# MainSheet.net
KiCad netlist of a schematic drawn in Altium Designer
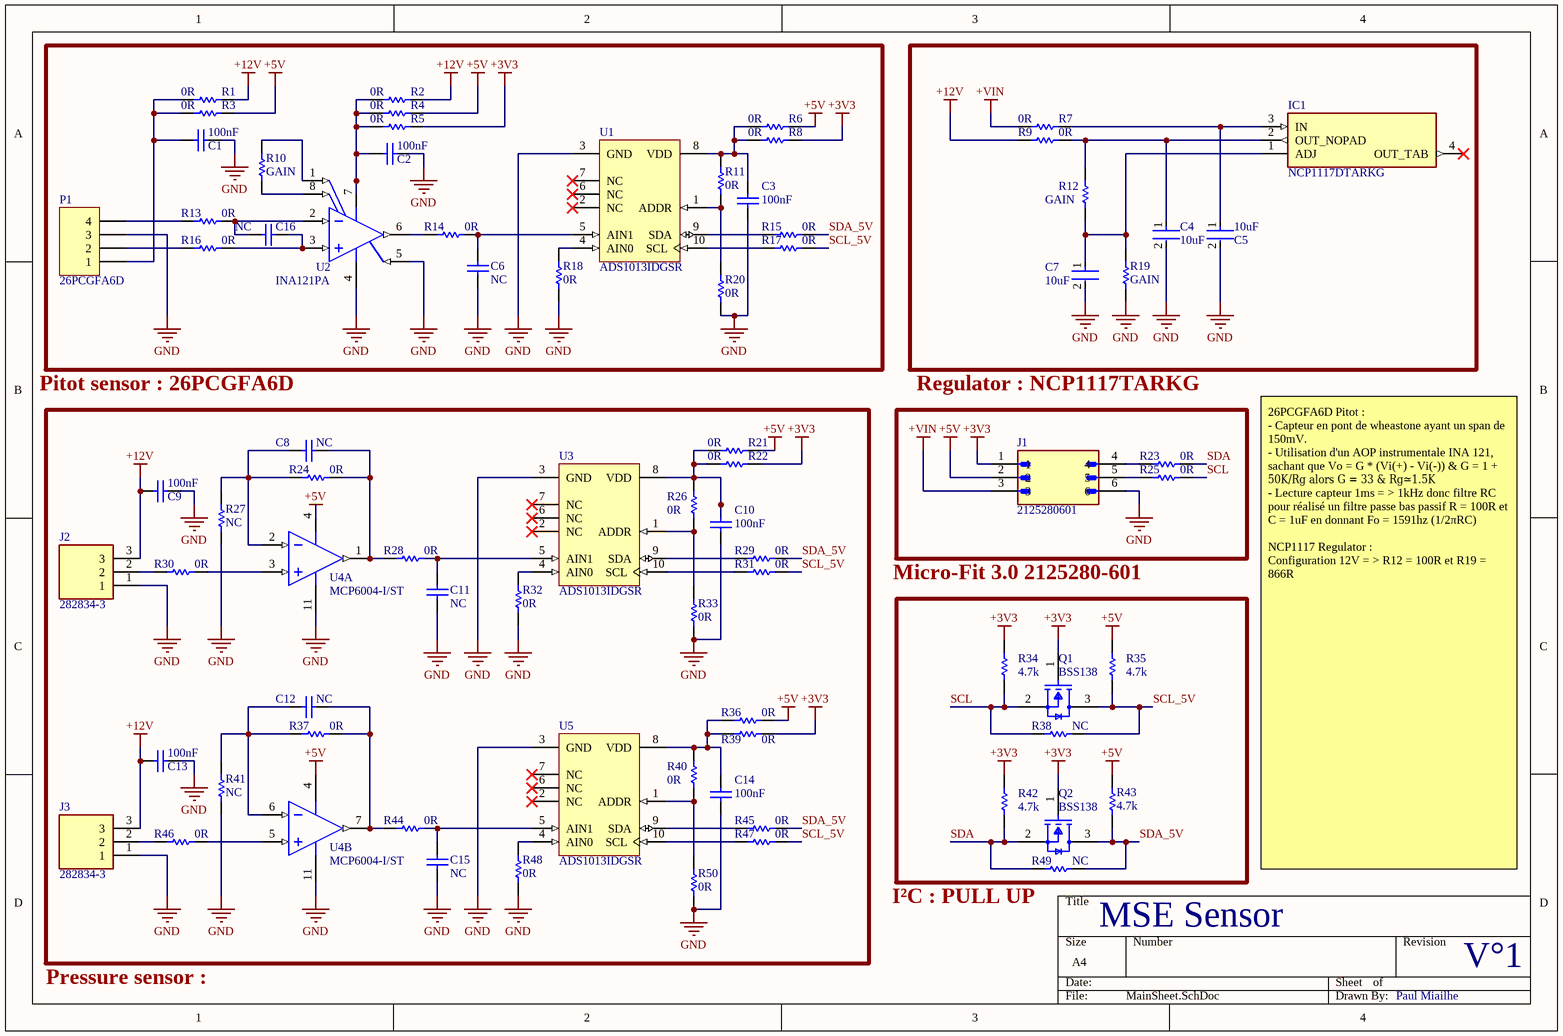
[diagram p0: MainSheet.SchDoc]

(export (version "E")
  (design (tool "Eeschema 10.0.6"))
  (components
    (comp (ref "C1")
      (value "GRM21BR71H104KA01L")
      (footprint "CAPC2013X135X45ML10T25")
      (description "Chip Capacitor, 0.1 uF, +/- 10%, 50 V, -55 to 125 degC, 0805 (2012 Metric), RoHS, Tape and Reel")
      (fields
        (field (name "VOLTAGE") "50V")
        (field (name "CAPACITANCE") "100nF")
        (field (name "TOLERANCE") "10%")
      )
      (libsource (lib "Altium Content Vault") (part "CAP-NP-2"))
    )
    (comp (ref "C2")
      (value "GRM21BR71H104KA01L")
      (footprint "CAPC2013X135X45ML10T25")
      (description "Chip Capacitor, 0.1 uF, +/- 10%, 50 V, -55 to 125 degC, 0805 (2012 Metric), RoHS, Tape and Reel")
      (fields
        (field (name "VOLTAGE") "50V")
        (field (name "CAPACITANCE") "100nF")
        (field (name "TOLERANCE") "10%")
      )
      (libsource (lib "Altium Content Vault") (part "CAP-NP-2"))
    )
    (comp (ref "C3")
      (value "GRM21BR71H104KA01L")
      (footprint "CAPC2013X135X45ML10T25")
      (description "Chip Capacitor, 0.1 uF, +/- 10%, 50 V, -55 to 125 degC, 0805 (2012 Metric), RoHS, Tape and Reel")
      (fields
        (field (name "VOLTAGE") "50V")
        (field (name "CAPACITANCE") "100nF")
        (field (name "TOLERANCE") "10%")
      )
      (libsource (lib "Altium Content Vault") (part "CAP-NP-2"))
    )
    (comp (ref "C4")
      (value "GRM21BR61E106KA73L")
      (footprint "FP-GRM21B-0_15-IPC_C")
      (description "Chip Multilayer Ceramic Capacitors for General Purpose, 0805, 10uF, X5R, 15%, 10%, 25V")
      (fields
        (field (name "VOLTAGE") "25V")
        (field (name "CAPACITANCE") "10uF")
        (field (name "TOLERANCE") "10%")
      )
      (libsource (lib "Altium Content Vault") (part "b4654b650e69147ec39a6b967a45e02"))
    )
    (comp (ref "C5")
      (value "GRM21BR61E106KA73L")
      (footprint "FP-GRM21B-0_15-IPC_C")
      (description "Chip Multilayer Ceramic Capacitors for General Purpose, 0805, 10uF, X5R, 15%, 10%, 25V")
      (fields
        (field (name "VOLTAGE") "25V")
        (field (name "CAPACITANCE") "10uF")
        (field (name "TOLERANCE") "10%")
      )
      (libsource (lib "Altium Content Vault") (part "b4654b650e69147ec39a6b967a45e02"))
    )
    (comp (ref "C6")
      (value "GRM21BR71H104KA01L")
      (footprint "CAPC2013X135X45ML10T25")
      (description "Chip Capacitor, 0.1 uF, +/- 10%, 50 V, -55 to 125 degC, 0805 (2012 Metric), RoHS, Tape and Reel")
      (fields
        (field (name "VOLTAGE") "50V")
        (field (name "CAPACITANCE") "NC")
        (field (name "TOLERANCE") "10%")
      )
      (libsource (lib "Altium Content Vault") (part "CAP-NP-2"))
    )
    (comp (ref "C7")
      (value "GRM21BR61E106KA73L")
      (footprint "FP-GRM21B-0_15-IPC_C")
      (description "Chip Multilayer Ceramic Capacitors for General Purpose, 0805, 10uF, X5R, 15%, 10%, 25V")
      (fields
        (field (name "VOLTAGE") "25V")
        (field (name "CAPACITANCE") "10uF")
        (field (name "TOLERANCE") "10%")
      )
      (libsource (lib "Altium Content Vault") (part "b4654b650e69147ec39a6b967a45e02"))
    )
    (comp (ref "C8")
      (value "GRM21BR71H104KA01L")
      (footprint "CAPC2013X135X45ML10T25")
      (description "Chip Capacitor, 0.1 uF, +/- 10%, 50 V, -55 to 125 degC, 0805 (2012 Metric), RoHS, Tape and Reel")
      (fields
        (field (name "VOLTAGE") "50V")
        (field (name "CAPACITANCE") "NC")
        (field (name "TOLERANCE") "10%")
      )
      (libsource (lib "Altium Content Vault") (part "CAP-NP-2"))
    )
    (comp (ref "C9")
      (value "GRM21BR71H104KA01L")
      (footprint "CAPC2013X135X45ML10T25")
      (description "Chip Capacitor, 0.1 uF, +/- 10%, 50 V, -55 to 125 degC, 0805 (2012 Metric), RoHS, Tape and Reel")
      (fields
        (field (name "VOLTAGE") "50V")
        (field (name "CAPACITANCE") "100nF")
        (field (name "TOLERANCE") "10%")
      )
      (libsource (lib "Altium Content Vault") (part "CAP-NP-2"))
    )
    (comp (ref "C10")
      (value "GRM21BR71H104KA01L")
      (footprint "CAPC2013X135X45ML10T25")
      (description "Chip Capacitor, 0.1 uF, +/- 10%, 50 V, -55 to 125 degC, 0805 (2012 Metric), RoHS, Tape and Reel")
      (fields
        (field (name "VOLTAGE") "50V")
        (field (name "CAPACITANCE") "100nF")
        (field (name "TOLERANCE") "10%")
      )
      (libsource (lib "Altium Content Vault") (part "CAP-NP-2"))
    )
    (comp (ref "C11")
      (value "GRM21BR71H104KA01L")
      (footprint "CAPC2013X135X45ML10T25")
      (description "Chip Capacitor, 0.1 uF, +/- 10%, 50 V, -55 to 125 degC, 0805 (2012 Metric), RoHS, Tape and Reel")
      (fields
        (field (name "VOLTAGE") "50V")
        (field (name "CAPACITANCE") "NC")
        (field (name "TOLERANCE") "10%")
      )
      (libsource (lib "Altium Content Vault") (part "CAP-NP-2"))
    )
    (comp (ref "C12")
      (value "GRM21BR71H104KA01L")
      (footprint "CAPC2013X135X45ML10T25")
      (description "Chip Capacitor, 0.1 uF, +/- 10%, 50 V, -55 to 125 degC, 0805 (2012 Metric), RoHS, Tape and Reel")
      (fields
        (field (name "VOLTAGE") "50V")
        (field (name "CAPACITANCE") "NC")
        (field (name "TOLERANCE") "10%")
      )
      (libsource (lib "Altium Content Vault") (part "CAP-NP-2"))
    )
    (comp (ref "C13")
      (value "GRM21BR71H104KA01L")
      (footprint "CAPC2013X135X45ML10T25")
      (description "Chip Capacitor, 0.1 uF, +/- 10%, 50 V, -55 to 125 degC, 0805 (2012 Metric), RoHS, Tape and Reel")
      (fields
        (field (name "VOLTAGE") "50V")
        (field (name "CAPACITANCE") "100nF")
        (field (name "TOLERANCE") "10%")
      )
      (libsource (lib "Altium Content Vault") (part "CAP-NP-2"))
    )
    (comp (ref "C14")
      (value "GRM21BR71H104KA01L")
      (footprint "CAPC2013X135X45ML10T25")
      (description "Chip Capacitor, 0.1 uF, +/- 10%, 50 V, -55 to 125 degC, 0805 (2012 Metric), RoHS, Tape and Reel")
      (fields
        (field (name "VOLTAGE") "50V")
        (field (name "CAPACITANCE") "100nF")
        (field (name "TOLERANCE") "10%")
      )
      (libsource (lib "Altium Content Vault") (part "CAP-NP-2"))
    )
    (comp (ref "C15")
      (value "GRM21BR71H104KA01L")
      (footprint "CAPC2013X135X45ML10T25")
      (description "Chip Capacitor, 0.1 uF, +/- 10%, 50 V, -55 to 125 degC, 0805 (2012 Metric), RoHS, Tape and Reel")
      (fields
        (field (name "VOLTAGE") "50V")
        (field (name "CAPACITANCE") "NC")
        (field (name "TOLERANCE") "10%")
      )
      (libsource (lib "Altium Content Vault") (part "CAP-NP-2"))
    )
    (comp (ref "C16")
      (value "GRM21BR71H104KA01L")
      (footprint "CAPC2013X135X45ML10T25")
      (description "Chip Capacitor, 0.1 uF, +/- 10%, 50 V, -55 to 125 degC, 0805 (2012 Metric), RoHS, Tape and Reel")
      (fields
        (field (name "VOLTAGE") "50V")
        (field (name "CAPACITANCE") "NC")
        (field (name "TOLERANCE") "10%")
      )
      (libsource (lib "Altium Content Vault") (part "CAP-NP-2"))
    )
    (comp (ref "IC1")
      (value "NCP1117DTARKG")
      (footprint "SamacSys:TO229P990X238-4N")
      (description "Integrated Circuit")
      (fields (field (name "MOUSER PART NUMBER") "863-NCP1117DTARKG"))
      (libsource (lib "*") (part "NCP1117DTARKG"))
    )
    (comp (ref "J1")
      (value "2125280601")
      (footprint "MOLEX_2125280601")
      (description "Connector Header Through Hole, Right Angle 6 position 0.118 (3.00mm)")
      (fields (field (name "MF") "Molex"))
      (libsource (lib "Saint-Étienne School of Mines- Mines Space") (part "2125280601"))
    )
    (comp (ref "J2")
      (value "282834-3")
      (footprint "SamacSys:2828343")
      (description "Connector")
      (fields (field (name "MOUSER PART NUMBER") "571-2828343"))
      (libsource (lib "*") (part "282834-3"))
    )
    (comp (ref "J3")
      (value "282834-3")
      (footprint "SamacSys:2828343")
      (description "Connector")
      (fields (field (name "MOUSER PART NUMBER") "571-2828343"))
      (libsource (lib "*") (part "282834-3"))
    )
    (comp (ref "P1")
      (value "26PCGFA6D")
      (footprint "HDR1X4")
      (description "Header, 4-Pin")
      (fields (field (name "PUBLISHER") "Altium Limited"))
      (libsource (lib "Miscellaneous Connectors") (part "Header 4"))
    )
    (comp (ref "Q1")
      (value "BSS138")
      (footprint "FP-318-08-IPC_B")
      (description "MOSFET N-CH 50V 220MA SOT-23")
      (libsource (lib "Altium Content Vault") (part "3b9c635fedb024a5347a57b145af9cc"))
    )
    (comp (ref "Q2")
      (value "BSS138")
      (footprint "FP-318-08-IPC_B")
      (description "MOSFET N-CH 50V 220MA SOT-23")
      (libsource (lib "Altium Content Vault") (part "3b9c635fedb024a5347a57b145af9cc"))
    )
    (comp (ref "R1")
      (value "0R")
      (footprint "RESC1608X55X25ML10T15")
      (description "Chip Resistor, 0 Ohm, +/- 5%, 0.1 W, -55 to 155 degC, 0603 (1608 Metric), RoHS, Tape and Reel")
      (fields (field (name "TOLERANCE") "5%") (field (name "MANUFACTURER") "Yageo"))
      (libsource (lib "Altium Content Vault") (part "RES-2"))
    )
    (comp (ref "R2")
      (value "0R")
      (footprint "RESC1608X55X25ML10T15")
      (description "Chip Resistor, 0 Ohm, +/- 5%, 0.1 W, -55 to 155 degC, 0603 (1608 Metric), RoHS, Tape and Reel")
      (fields (field (name "TOLERANCE") "5%") (field (name "MANUFACTURER") "Yageo"))
      (libsource (lib "Altium Content Vault") (part "RES-2"))
    )
    (comp (ref "R3")
      (value "0R")
      (footprint "RESC1608X55X25ML10T15")
      (description "Chip Resistor, 0 Ohm, +/- 5%, 0.1 W, -55 to 155 degC, 0603 (1608 Metric), RoHS, Tape and Reel")
      (fields (field (name "TOLERANCE") "5%") (field (name "MANUFACTURER") "Yageo"))
      (libsource (lib "Altium Content Vault") (part "RES-2"))
    )
    (comp (ref "R4")
      (value "0R")
      (footprint "RESC1608X55X25ML10T15")
      (description "Chip Resistor, 0 Ohm, +/- 5%, 0.1 W, -55 to 155 degC, 0603 (1608 Metric), RoHS, Tape and Reel")
      (fields (field (name "TOLERANCE") "5%") (field (name "MANUFACTURER") "Yageo"))
      (libsource (lib "Altium Content Vault") (part "RES-2"))
    )
    (comp (ref "R5")
      (value "0R")
      (footprint "RESC1608X55X25ML10T15")
      (description "Chip Resistor, 0 Ohm, +/- 5%, 0.1 W, -55 to 155 degC, 0603 (1608 Metric), RoHS, Tape and Reel")
      (fields (field (name "TOLERANCE") "5%") (field (name "MANUFACTURER") "Yageo"))
      (libsource (lib "Altium Content Vault") (part "RES-2"))
    )
    (comp (ref "R6")
      (value "0R")
      (footprint "RESC1608X55X25ML10T15")
      (description "Chip Resistor, 0 Ohm, +/- 5%, 0.1 W, -55 to 155 degC, 0603 (1608 Metric), RoHS, Tape and Reel")
      (fields (field (name "TOLERANCE") "5%") (field (name "MANUFACTURER") "Yageo"))
      (libsource (lib "Altium Content Vault") (part "RES-2"))
    )
    (comp (ref "R7")
      (value "0R")
      (footprint "RESC1608X55X25ML10T15")
      (description "Chip Resistor, 0 Ohm, +/- 5%, 0.1 W, -55 to 155 degC, 0603 (1608 Metric), RoHS, Tape and Reel")
      (fields (field (name "TOLERANCE") "5%") (field (name "MANUFACTURER") "Yageo"))
      (libsource (lib "Altium Content Vault") (part "RES-2"))
    )
    (comp (ref "R8")
      (value "0R")
      (footprint "RESC1608X55X25ML10T15")
      (description "Chip Resistor, 0 Ohm, +/- 5%, 0.1 W, -55 to 155 degC, 0603 (1608 Metric), RoHS, Tape and Reel")
      (fields (field (name "TOLERANCE") "5%") (field (name "MANUFACTURER") "Yageo"))
      (libsource (lib "Altium Content Vault") (part "RES-2"))
    )
    (comp (ref "R9")
      (value "0R")
      (footprint "RESC1608X55X25ML10T15")
      (description "Chip Resistor, 0 Ohm, +/- 5%, 0.1 W, -55 to 155 degC, 0603 (1608 Metric), RoHS, Tape and Reel")
      (fields (field (name "TOLERANCE") "5%") (field (name "MANUFACTURER") "Yageo"))
      (libsource (lib "Altium Content Vault") (part "RES-2"))
    )
    (comp (ref "R10")
      (value "GAIN")
      (footprint "RESC1608X55X25ML10T15")
      (description "Chip Resistor, 0 Ohm, +/- 5%, 0.1 W, -55 to 155 degC, 0603 (1608 Metric), RoHS, Tape and Reel")
      (fields (field (name "TOLERANCE") "5%") (field (name "MANUFACTURER") "Yageo"))
      (libsource (lib "Altium Content Vault") (part "RES-2"))
    )
    (comp (ref "R11")
      (value "0R")
      (footprint "RESC1608X55X25ML10T15")
      (description "Chip Resistor, 0 Ohm, +/- 5%, 0.1 W, -55 to 155 degC, 0603 (1608 Metric), RoHS, Tape and Reel")
      (fields (field (name "TOLERANCE") "5%") (field (name "MANUFACTURER") "Yageo"))
      (libsource (lib "Altium Content Vault") (part "RES-2"))
    )
    (comp (ref "R12")
      (value "GAIN")
      (footprint "RESC1608X55X25ML10T15")
      (description "Chip Resistor, 0 Ohm, +/- 5%, 0.1 W, -55 to 155 degC, 0603 (1608 Metric), RoHS, Tape and Reel")
      (fields (field (name "TOLERANCE") "5%") (field (name "MANUFACTURER") "Yageo"))
      (libsource (lib "Altium Content Vault") (part "RES-2"))
    )
    (comp (ref "R13")
      (value "0R")
      (footprint "RESC1608X55X25ML10T15")
      (description "Chip Resistor, 0 Ohm, +/- 5%, 0.1 W, -55 to 155 degC, 0603 (1608 Metric), RoHS, Tape and Reel")
      (fields (field (name "TOLERANCE") "5%") (field (name "MANUFACTURER") "Yageo"))
      (libsource (lib "Altium Content Vault") (part "RES-2"))
    )
    (comp (ref "R14")
      (value "0R")
      (footprint "RESC1608X55X25ML10T15")
      (description "Chip Resistor, 0 Ohm, +/- 5%, 0.1 W, -55 to 155 degC, 0603 (1608 Metric), RoHS, Tape and Reel")
      (fields (field (name "TOLERANCE") "5%") (field (name "MANUFACTURER") "Yageo"))
      (libsource (lib "Altium Content Vault") (part "RES-2"))
    )
    (comp (ref "R15")
      (value "0R")
      (footprint "RESC1608X55X25ML10T15")
      (description "Chip Resistor, 0 Ohm, +/- 5%, 0.1 W, -55 to 155 degC, 0603 (1608 Metric), RoHS, Tape and Reel")
      (fields (field (name "TOLERANCE") "5%") (field (name "MANUFACTURER") "Yageo"))
      (libsource (lib "Altium Content Vault") (part "RES-2"))
    )
    (comp (ref "R16")
      (value "0R")
      (footprint "RESC1608X55X25ML10T15")
      (description "Chip Resistor, 0 Ohm, +/- 5%, 0.1 W, -55 to 155 degC, 0603 (1608 Metric), RoHS, Tape and Reel")
      (fields (field (name "TOLERANCE") "5%") (field (name "MANUFACTURER") "Yageo"))
      (libsource (lib "Altium Content Vault") (part "RES-2"))
    )
    (comp (ref "R17")
      (value "0R")
      (footprint "RESC1608X55X25ML10T15")
      (description "Chip Resistor, 0 Ohm, +/- 5%, 0.1 W, -55 to 155 degC, 0603 (1608 Metric), RoHS, Tape and Reel")
      (fields (field (name "TOLERANCE") "5%") (field (name "MANUFACTURER") "Yageo"))
      (libsource (lib "Altium Content Vault") (part "RES-2"))
    )
    (comp (ref "R18")
      (value "0R")
      (footprint "RESC1608X55X25ML10T15")
      (description "Chip Resistor, 0 Ohm, +/- 5%, 0.1 W, -55 to 155 degC, 0603 (1608 Metric), RoHS, Tape and Reel")
      (fields (field (name "TOLERANCE") "5%") (field (name "MANUFACTURER") "Yageo"))
      (libsource (lib "Altium Content Vault") (part "RES-2"))
    )
    (comp (ref "R19")
      (value "GAIN")
      (footprint "RESC1608X55X25ML10T15")
      (description "Chip Resistor, 0 Ohm, +/- 5%, 0.1 W, -55 to 155 degC, 0603 (1608 Metric), RoHS, Tape and Reel")
      (fields (field (name "TOLERANCE") "5%") (field (name "MANUFACTURER") "Yageo"))
      (libsource (lib "Altium Content Vault") (part "RES-2"))
    )
    (comp (ref "R20")
      (value "0R")
      (footprint "RESC1608X55X25ML10T15")
      (description "Chip Resistor, 0 Ohm, +/- 5%, 0.1 W, -55 to 155 degC, 0603 (1608 Metric), RoHS, Tape and Reel")
      (fields (field (name "TOLERANCE") "5%") (field (name "MANUFACTURER") "Yageo"))
      (libsource (lib "Altium Content Vault") (part "RES-2"))
    )
    (comp (ref "R21")
      (value "0R")
      (footprint "RESC1608X55X25ML10T15")
      (description "Chip Resistor, 0 Ohm, +/- 5%, 0.1 W, -55 to 155 degC, 0603 (1608 Metric), RoHS, Tape and Reel")
      (fields (field (name "TOLERANCE") "5%") (field (name "MANUFACTURER") "Yageo"))
      (libsource (lib "Altium Content Vault") (part "RES-2"))
    )
    (comp (ref "R22")
      (value "0R")
      (footprint "RESC1608X55X25ML10T15")
      (description "Chip Resistor, 0 Ohm, +/- 5%, 0.1 W, -55 to 155 degC, 0603 (1608 Metric), RoHS, Tape and Reel")
      (fields (field (name "TOLERANCE") "5%") (field (name "MANUFACTURER") "Yageo"))
      (libsource (lib "Altium Content Vault") (part "RES-2"))
    )
    (comp (ref "R23")
      (value "0R")
      (footprint "RESC1608X55X25ML10T15")
      (description "Chip Resistor, 0 Ohm, +/- 5%, 0.1 W, -55 to 155 degC, 0603 (1608 Metric), RoHS, Tape and Reel")
      (fields (field (name "TOLERANCE") "5%") (field (name "MANUFACTURER") "Yageo"))
      (libsource (lib "Altium Content Vault") (part "RES-2"))
    )
    (comp (ref "R24")
      (value "0R")
      (footprint "RESC1608X55X25ML10T15")
      (description "Chip Resistor, 0 Ohm, +/- 5%, 0.1 W, -55 to 155 degC, 0603 (1608 Metric), RoHS, Tape and Reel")
      (fields (field (name "TOLERANCE") "5%") (field (name "MANUFACTURER") "Yageo"))
      (libsource (lib "Altium Content Vault") (part "RES-2"))
    )
    (comp (ref "R25")
      (value "0R")
      (footprint "RESC1608X55X25ML10T15")
      (description "Chip Resistor, 0 Ohm, +/- 5%, 0.1 W, -55 to 155 degC, 0603 (1608 Metric), RoHS, Tape and Reel")
      (fields (field (name "TOLERANCE") "5%") (field (name "MANUFACTURER") "Yageo"))
      (libsource (lib "Altium Content Vault") (part "RES-2"))
    )
    (comp (ref "R26")
      (value "0R")
      (footprint "RESC1608X55X25ML10T15")
      (description "Chip Resistor, 0 Ohm, +/- 5%, 0.1 W, -55 to 155 degC, 0603 (1608 Metric), RoHS, Tape and Reel")
      (fields (field (name "TOLERANCE") "5%") (field (name "MANUFACTURER") "Yageo"))
      (libsource (lib "Altium Content Vault") (part "RES-2"))
    )
    (comp (ref "R27")
      (value "NC")
      (footprint "RESC1608X55X25ML10T15")
      (description "Chip Resistor, 0 Ohm, +/- 5%, 0.1 W, -55 to 155 degC, 0603 (1608 Metric), RoHS, Tape and Reel")
      (fields (field (name "TOLERANCE") "5%") (field (name "MANUFACTURER") "Yageo"))
      (libsource (lib "Altium Content Vault") (part "RES-2"))
    )
    (comp (ref "R28")
      (value "0R")
      (footprint "RESC1608X55X25ML10T15")
      (description "Chip Resistor, 0 Ohm, +/- 5%, 0.1 W, -55 to 155 degC, 0603 (1608 Metric), RoHS, Tape and Reel")
      (fields (field (name "TOLERANCE") "5%") (field (name "MANUFACTURER") "Yageo"))
      (libsource (lib "Altium Content Vault") (part "RES-2"))
    )
    (comp (ref "R29")
      (value "0R")
      (footprint "RESC1608X55X25ML10T15")
      (description "Chip Resistor, 0 Ohm, +/- 5%, 0.1 W, -55 to 155 degC, 0603 (1608 Metric), RoHS, Tape and Reel")
      (fields (field (name "TOLERANCE") "5%") (field (name "MANUFACTURER") "Yageo"))
      (libsource (lib "Altium Content Vault") (part "RES-2"))
    )
    (comp (ref "R30")
      (value "0R")
      (footprint "RESC1608X55X25ML10T15")
      (description "Chip Resistor, 0 Ohm, +/- 5%, 0.1 W, -55 to 155 degC, 0603 (1608 Metric), RoHS, Tape and Reel")
      (fields (field (name "TOLERANCE") "5%") (field (name "MANUFACTURER") "Yageo"))
      (libsource (lib "Altium Content Vault") (part "RES-2"))
    )
    (comp (ref "R31")
      (value "0R")
      (footprint "RESC1608X55X25ML10T15")
      (description "Chip Resistor, 0 Ohm, +/- 5%, 0.1 W, -55 to 155 degC, 0603 (1608 Metric), RoHS, Tape and Reel")
      (fields (field (name "TOLERANCE") "5%") (field (name "MANUFACTURER") "Yageo"))
      (libsource (lib "Altium Content Vault") (part "RES-2"))
    )
    (comp (ref "R32")
      (value "0R")
      (footprint "RESC1608X55X25ML10T15")
      (description "Chip Resistor, 0 Ohm, +/- 5%, 0.1 W, -55 to 155 degC, 0603 (1608 Metric), RoHS, Tape and Reel")
      (fields (field (name "TOLERANCE") "5%") (field (name "MANUFACTURER") "Yageo"))
      (libsource (lib "Altium Content Vault") (part "RES-2"))
    )
    (comp (ref "R33")
      (value "0R")
      (footprint "RESC1608X55X25ML10T15")
      (description "Chip Resistor, 0 Ohm, +/- 5%, 0.1 W, -55 to 155 degC, 0603 (1608 Metric), RoHS, Tape and Reel")
      (fields (field (name "TOLERANCE") "5%") (field (name "MANUFACTURER") "Yageo"))
      (libsource (lib "Altium Content Vault") (part "RES-2"))
    )
    (comp (ref "R34")
      (value "RC0603FR-074K7L")
      (footprint "RESC1608X55X25LL10T15")
      (description "Chip Resistor, 4.7 KOhm, +/- 1%, 0.1 W, -55 to 155 degC, 0603 (1608 Metric), RoHS, Tape and Reel")
      (fields
        (field (name "MANUFACTURER") "Yageo")
        (field (name "RESISTANCE") "4.7k")
        (field (name "TOLERANCE") "1%")
      )
      (libsource (lib "Altium Content Vault") (part "RES-2"))
    )
    (comp (ref "R35")
      (value "RC0603FR-074K7L")
      (footprint "RESC1608X55X25LL10T15")
      (description "Chip Resistor, 4.7 KOhm, +/- 1%, 0.1 W, -55 to 155 degC, 0603 (1608 Metric), RoHS, Tape and Reel")
      (fields
        (field (name "MANUFACTURER") "Yageo")
        (field (name "RESISTANCE") "4.7k")
        (field (name "TOLERANCE") "1%")
      )
      (libsource (lib "Altium Content Vault") (part "RES-2"))
    )
    (comp (ref "R36")
      (value "0R")
      (footprint "RESC1608X55X25ML10T15")
      (description "Chip Resistor, 0 Ohm, +/- 5%, 0.1 W, -55 to 155 degC, 0603 (1608 Metric), RoHS, Tape and Reel")
      (fields (field (name "TOLERANCE") "5%") (field (name "MANUFACTURER") "Yageo"))
      (libsource (lib "Altium Content Vault") (part "RES-2"))
    )
    (comp (ref "R37")
      (value "0R")
      (footprint "RESC1608X55X25ML10T15")
      (description "Chip Resistor, 0 Ohm, +/- 5%, 0.1 W, -55 to 155 degC, 0603 (1608 Metric), RoHS, Tape and Reel")
      (fields (field (name "TOLERANCE") "5%") (field (name "MANUFACTURER") "Yageo"))
      (libsource (lib "Altium Content Vault") (part "RES-2"))
    )
    (comp (ref "R38")
      (value "NC")
      (footprint "RESC1608X55X25ML10T15")
      (description "Chip Resistor, 0 Ohm, +/- 5%, 0.1 W, -55 to 155 degC, 0603 (1608 Metric), RoHS, Tape and Reel")
      (fields (field (name "TOLERANCE") "5%") (field (name "MANUFACTURER") "Yageo"))
      (libsource (lib "Altium Content Vault") (part "RES-2"))
    )
    (comp (ref "R39")
      (value "0R")
      (footprint "RESC1608X55X25ML10T15")
      (description "Chip Resistor, 0 Ohm, +/- 5%, 0.1 W, -55 to 155 degC, 0603 (1608 Metric), RoHS, Tape and Reel")
      (fields (field (name "TOLERANCE") "5%") (field (name "MANUFACTURER") "Yageo"))
      (libsource (lib "Altium Content Vault") (part "RES-2"))
    )
    (comp (ref "R40")
      (value "0R")
      (footprint "RESC1608X55X25ML10T15")
      (description "Chip Resistor, 0 Ohm, +/- 5%, 0.1 W, -55 to 155 degC, 0603 (1608 Metric), RoHS, Tape and Reel")
      (fields (field (name "TOLERANCE") "5%") (field (name "MANUFACTURER") "Yageo"))
      (libsource (lib "Altium Content Vault") (part "RES-2"))
    )
    (comp (ref "R41")
      (value "NC")
      (footprint "RESC1608X55X25ML10T15")
      (description "Chip Resistor, 0 Ohm, +/- 5%, 0.1 W, -55 to 155 degC, 0603 (1608 Metric), RoHS, Tape and Reel")
      (fields (field (name "TOLERANCE") "5%") (field (name "MANUFACTURER") "Yageo"))
      (libsource (lib "Altium Content Vault") (part "RES-2"))
    )
    (comp (ref "R42")
      (value "RC0603FR-074K7L")
      (footprint "RESC1608X55X25LL10T15")
      (description "Chip Resistor, 4.7 KOhm, +/- 1%, 0.1 W, -55 to 155 degC, 0603 (1608 Metric), RoHS, Tape and Reel")
      (fields
        (field (name "MANUFACTURER") "Yageo")
        (field (name "RESISTANCE") "4.7k")
        (field (name "TOLERANCE") "1%")
      )
      (libsource (lib "Altium Content Vault") (part "RES-2"))
    )
    (comp (ref "R43")
      (value "RC0603FR-074K7L")
      (footprint "RESC1608X55X25LL10T15")
      (description "Chip Resistor, 4.7 KOhm, +/- 1%, 0.1 W, -55 to 155 degC, 0603 (1608 Metric), RoHS, Tape and Reel")
      (fields
        (field (name "MANUFACTURER") "Yageo")
        (field (name "RESISTANCE") "4.7k")
        (field (name "TOLERANCE") "1%")
      )
      (libsource (lib "Altium Content Vault") (part "RES-2"))
    )
    (comp (ref "R44")
      (value "0R")
      (footprint "RESC1608X55X25ML10T15")
      (description "Chip Resistor, 0 Ohm, +/- 5%, 0.1 W, -55 to 155 degC, 0603 (1608 Metric), RoHS, Tape and Reel")
      (fields (field (name "TOLERANCE") "5%") (field (name "MANUFACTURER") "Yageo"))
      (libsource (lib "Altium Content Vault") (part "RES-2"))
    )
    (comp (ref "R45")
      (value "0R")
      (footprint "RESC1608X55X25ML10T15")
      (description "Chip Resistor, 0 Ohm, +/- 5%, 0.1 W, -55 to 155 degC, 0603 (1608 Metric), RoHS, Tape and Reel")
      (fields (field (name "TOLERANCE") "5%") (field (name "MANUFACTURER") "Yageo"))
      (libsource (lib "Altium Content Vault") (part "RES-2"))
    )
    (comp (ref "R46")
      (value "0R")
      (footprint "RESC1608X55X25ML10T15")
      (description "Chip Resistor, 0 Ohm, +/- 5%, 0.1 W, -55 to 155 degC, 0603 (1608 Metric), RoHS, Tape and Reel")
      (fields (field (name "TOLERANCE") "5%") (field (name "MANUFACTURER") "Yageo"))
      (libsource (lib "Altium Content Vault") (part "RES-2"))
    )
    (comp (ref "R47")
      (value "0R")
      (footprint "RESC1608X55X25ML10T15")
      (description "Chip Resistor, 0 Ohm, +/- 5%, 0.1 W, -55 to 155 degC, 0603 (1608 Metric), RoHS, Tape and Reel")
      (fields (field (name "TOLERANCE") "5%") (field (name "MANUFACTURER") "Yageo"))
      (libsource (lib "Altium Content Vault") (part "RES-2"))
    )
    (comp (ref "R48")
      (value "0R")
      (footprint "RESC1608X55X25ML10T15")
      (description "Chip Resistor, 0 Ohm, +/- 5%, 0.1 W, -55 to 155 degC, 0603 (1608 Metric), RoHS, Tape and Reel")
      (fields (field (name "TOLERANCE") "5%") (field (name "MANUFACTURER") "Yageo"))
      (libsource (lib "Altium Content Vault") (part "RES-2"))
    )
    (comp (ref "R49")
      (value "NC")
      (footprint "RESC1608X55X25ML10T15")
      (description "Chip Resistor, 0 Ohm, +/- 5%, 0.1 W, -55 to 155 degC, 0603 (1608 Metric), RoHS, Tape and Reel")
      (fields (field (name "TOLERANCE") "5%") (field (name "MANUFACTURER") "Yageo"))
      (libsource (lib "Altium Content Vault") (part "RES-2"))
    )
    (comp (ref "R50")
      (value "0R")
      (footprint "RESC1608X55X25ML10T15")
      (description "Chip Resistor, 0 Ohm, +/- 5%, 0.1 W, -55 to 155 degC, 0603 (1608 Metric), RoHS, Tape and Reel")
      (fields (field (name "TOLERANCE") "5%") (field (name "MANUFACTURER") "Yageo"))
      (libsource (lib "Altium Content Vault") (part "RES-2"))
    )
    (comp (ref "U1")
      (value "ADS1013IDGSR")
      (footprint "TI-DGS10_N")
      (fields (field (name "MANUFACTURER") "Texas Instruments"))
      (libsource (lib "Altium Content Vault") (part "TI-ADS1X13XXX10"))
    )
    (comp (ref "U2")
      (value "INA121PA")
      (footprint "P0008A")
      (fields (field (name "MANUFACTURER") "Texas Instruments"))
      (libsource (lib "Altium Content Vault") (part "TI-INA1XX-8"))
    )
    (comp (ref "U3")
      (value "ADS1013IDGSR")
      (footprint "TI-DGS10_N")
      (fields (field (name "MANUFACTURER") "Texas Instruments"))
      (libsource (lib "Altium Content Vault") (part "TI-ADS1X13XXX10"))
    )
    (comp (ref "U4")
      (value "MCP6004-I/ST")
      (footprint "TSSOP-ST14_M")
      (description "None")
      (libsource (lib "Altium Content Vault") (part "AMP-OPA-MCP6004-IL14"))
    )
    (comp (ref "U5")
      (value "ADS1013IDGSR")
      (footprint "TI-DGS10_N")
      (fields (field (name "MANUFACTURER") "Texas Instruments"))
      (libsource (lib "Altium Content Vault") (part "TI-ADS1X13XXX10"))
    )
  )
  (nets
    (net (code "1") (name "+3V3") (class "Default")
      (node (ref "J1") (pin "1") (pinfunction "1_1") (pintype "passive"))
      (node (ref "Q1") (pin "1") (pinfunction "G_1") (pintype "passive"))
      (node (ref "Q2") (pin "1") (pinfunction "G_1") (pintype "passive"))
      (node (ref "R22") (pin "2") (pinfunction "2_2") (pintype "passive"))
      (node (ref "R34") (pin "2") (pinfunction "2_2") (pintype "passive"))
      (node (ref "R39") (pin "2") (pinfunction "2_2") (pintype "passive"))
      (node (ref "R42") (pin "2") (pinfunction "2_2") (pintype "passive"))
      (node (ref "R5") (pin "1") (pinfunction "1_1") (pintype "passive"))
      (node (ref "R8") (pin "2") (pinfunction "2_2") (pintype "passive"))
    )
    (net (code "2") (name "+5V") (class "Default")
      (node (ref "J1") (pin "2") (pinfunction "2_2") (pintype "passive"))
      (node (ref "R21") (pin "2") (pinfunction "2_2") (pintype "passive"))
      (node (ref "R3") (pin "1") (pinfunction "1_1") (pintype "passive"))
      (node (ref "R35") (pin "2") (pinfunction "2_2") (pintype "passive"))
      (node (ref "R36") (pin "2") (pinfunction "2_2") (pintype "passive"))
      (node (ref "R4") (pin "1") (pinfunction "1_1") (pintype "passive"))
      (node (ref "R43") (pin "2") (pinfunction "2_2") (pintype "passive"))
      (node (ref "R6") (pin "2") (pinfunction "2_2") (pintype "passive"))
      (node (ref "U4") (pin "4") (pinfunction "VDD_4") (pintype "power_in"))
    )
    (net (code "3") (name "+12V") (class "Default")
      (node (ref "C13") (pin "2") (pinfunction "2_2") (pintype "passive"))
      (node (ref "C9") (pin "2") (pinfunction "2_2") (pintype "passive"))
      (node (ref "J2") (pin "3") (pinfunction "3_3") (pintype "passive"))
      (node (ref "J3") (pin "3") (pinfunction "3_3") (pintype "passive"))
      (node (ref "R1") (pin "1") (pinfunction "1_1") (pintype "passive"))
      (node (ref "R2") (pin "1") (pinfunction "1_1") (pintype "passive"))
      (node (ref "R9") (pin "1") (pinfunction "1_1") (pintype "passive"))
    )
    (net (code "4") (name "+VIN") (class "Default")
      (node (ref "J1") (pin "3") (pinfunction "3_3") (pintype "passive"))
      (node (ref "R7") (pin "1") (pinfunction "1_1") (pintype "passive"))
    )
    (net (code "5") (name "/SCL") (class "Default")
      (node (ref "Q1") (pin "2") (pinfunction "S_2") (pintype "passive"))
      (node (ref "R25") (pin "2") (pinfunction "2_2") (pintype "passive"))
      (node (ref "R34") (pin "1") (pinfunction "1_1") (pintype "passive"))
      (node (ref "R38") (pin "1") (pinfunction "1_1") (pintype "passive"))
    )
    (net (code "6") (name "/SCL_5V") (class "Default")
      (node (ref "Q1") (pin "3") (pinfunction "D_3") (pintype "passive"))
      (node (ref "R17") (pin "2") (pinfunction "2_2") (pintype "passive"))
      (node (ref "R31") (pin "2") (pinfunction "2_2") (pintype "passive"))
      (node (ref "R35") (pin "1") (pinfunction "1_1") (pintype "passive"))
      (node (ref "R38") (pin "2") (pinfunction "2_2") (pintype "passive"))
      (node (ref "R47") (pin "2") (pinfunction "2_2") (pintype "passive"))
    )
    (net (code "7") (name "/SDA") (class "Default")
      (node (ref "Q2") (pin "2") (pinfunction "S_2") (pintype "passive"))
      (node (ref "R23") (pin "2") (pinfunction "2_2") (pintype "passive"))
      (node (ref "R42") (pin "1") (pinfunction "1_1") (pintype "passive"))
      (node (ref "R49") (pin "1") (pinfunction "1_1") (pintype "passive"))
    )
    (net (code "8") (name "/SDA_5V") (class "Default")
      (node (ref "Q2") (pin "3") (pinfunction "D_3") (pintype "passive"))
      (node (ref "R15") (pin "2") (pinfunction "2_2") (pintype "passive"))
      (node (ref "R29") (pin "2") (pinfunction "2_2") (pintype "passive"))
      (node (ref "R43") (pin "1") (pinfunction "1_1") (pintype "passive"))
      (node (ref "R45") (pin "2") (pinfunction "2_2") (pintype "passive"))
      (node (ref "R49") (pin "2") (pinfunction "2_2") (pintype "passive"))
    )
    (net (code "9") (name "GND") (class "Default")
      (node (ref "C1") (pin "1") (pinfunction "1_1") (pintype "passive"))
      (node (ref "C10") (pin "1") (pinfunction "1_1") (pintype "passive"))
      (node (ref "C11") (pin "2") (pinfunction "2_2") (pintype "passive"))
      (node (ref "C13") (pin "1") (pinfunction "1_1") (pintype "passive"))
      (node (ref "C14") (pin "1") (pinfunction "1_1") (pintype "passive"))
      (node (ref "C15") (pin "2") (pinfunction "2_2") (pintype "passive"))
      (node (ref "C2") (pin "1") (pinfunction "1_1") (pintype "passive"))
      (node (ref "C3") (pin "1") (pinfunction "1_1") (pintype "passive"))
      (node (ref "C4") (pin "2") (pinfunction "2_2") (pintype "passive"))
      (node (ref "C5") (pin "2") (pinfunction "2_2") (pintype "passive"))
      (node (ref "C6") (pin "2") (pinfunction "2_2") (pintype "passive"))
      (node (ref "C7") (pin "2") (pinfunction "2_2") (pintype "passive"))
      (node (ref "C9") (pin "1") (pinfunction "1_1") (pintype "passive"))
      (node (ref "J1") (pin "6") (pinfunction "6_6") (pintype "passive"))
      (node (ref "J2") (pin "1") (pinfunction "1_1") (pintype "passive"))
      (node (ref "J3") (pin "1") (pinfunction "1_1") (pintype "passive"))
      (node (ref "P1") (pin "3") (pinfunction "3_3") (pintype "passive"))
      (node (ref "R18") (pin "1") (pinfunction "1_1") (pintype "passive"))
      (node (ref "R19") (pin "1") (pinfunction "1_1") (pintype "passive"))
      (node (ref "R20") (pin "2") (pinfunction "2_2") (pintype "passive"))
      (node (ref "R27") (pin "1") (pinfunction "1_1") (pintype "passive"))
      (node (ref "R32") (pin "1") (pinfunction "1_1") (pintype "passive"))
      (node (ref "R33") (pin "2") (pinfunction "2_2") (pintype "passive"))
      (node (ref "R41") (pin "1") (pinfunction "1_1") (pintype "passive"))
      (node (ref "R48") (pin "1") (pinfunction "1_1") (pintype "passive"))
      (node (ref "R50") (pin "2") (pinfunction "2_2") (pintype "passive"))
      (node (ref "U1") (pin "3") (pinfunction "GND_3") (pintype "power_in"))
      (node (ref "U2") (pin "4") (pinfunction "V-_4") (pintype "power_in"))
      (node (ref "U2") (pin "5") (pinfunction "REF_5") (pintype "input"))
      (node (ref "U3") (pin "3") (pinfunction "GND_3") (pintype "power_in"))
      (node (ref "U4") (pin "11") (pinfunction "VSS_11") (pintype "power_in"))
      (node (ref "U5") (pin "3") (pinfunction "GND_3") (pintype "power_in"))
    )
    (net (code "10") (name "Net-(C1-Pad2)") (class "Default")
      (node (ref "C1") (pin "2") (pinfunction "2_2") (pintype "passive"))
      (node (ref "P1") (pin "1") (pinfunction "1_1") (pintype "passive"))
      (node (ref "R1") (pin "2") (pinfunction "2_2") (pintype "passive"))
      (node (ref "R3") (pin "2") (pinfunction "2_2") (pintype "passive"))
    )
    (net (code "11") (name "Net-(IC1-ADJ)") (class "Default")
      (node (ref "C7") (pin "1") (pinfunction "1_1") (pintype "passive"))
      (node (ref "IC1") (pin "1") (pinfunction "ADJ_1") (pintype "power_in"))
      (node (ref "R12") (pin "2") (pinfunction "2_2") (pintype "passive"))
      (node (ref "R19") (pin "2") (pinfunction "2_2") (pintype "passive"))
    )
    (net (code "12") (name "Net-(IC1-IN)") (class "Default")
      (node (ref "C5") (pin "1") (pinfunction "1_1") (pintype "passive"))
      (node (ref "IC1") (pin "3") (pinfunction "IN_3") (pintype "input"))
      (node (ref "R7") (pin "2") (pinfunction "2_2") (pintype "passive"))
    )
    (net (code "13") (name "Net-(IC1-OUT_NOPAD)") (class "Default")
      (node (ref "C4") (pin "1") (pinfunction "1_1") (pintype "passive"))
      (node (ref "IC1") (pin "2") (pinfunction "OUT_NOPAD_2") (pintype "output"))
      (node (ref "R12") (pin "1") (pinfunction "1_1") (pintype "passive"))
      (node (ref "R9") (pin "2") (pinfunction "2_2") (pintype "passive"))
    )
    (net (code "14") (name "Net-(J1-Pad4)") (class "Default")
      (node (ref "J1") (pin "4") (pinfunction "4_4") (pintype "passive"))
      (node (ref "R23") (pin "1") (pinfunction "1_1") (pintype "passive"))
    )
    (net (code "15") (name "Net-(J1-Pad5)") (class "Default")
      (node (ref "J1") (pin "5") (pinfunction "5_5") (pintype "passive"))
      (node (ref "R25") (pin "1") (pinfunction "1_1") (pintype "passive"))
    )
    (net (code "16") (name "Net-(J2-Pad2)") (class "Default")
      (node (ref "J2") (pin "2") (pinfunction "2_2") (pintype "passive"))
      (node (ref "R30") (pin "2") (pinfunction "2_2") (pintype "passive"))
    )
    (net (code "17") (name "Net-(J3-Pad2)") (class "Default")
      (node (ref "J3") (pin "2") (pinfunction "2_2") (pintype "passive"))
      (node (ref "R46") (pin "2") (pinfunction "2_2") (pintype "passive"))
    )
    (net (code "18") (name "Net-(P1-Pad2)") (class "Default")
      (node (ref "P1") (pin "2") (pinfunction "2_2") (pintype "passive"))
      (node (ref "R16") (pin "2") (pinfunction "2_2") (pintype "passive"))
    )
    (net (code "19") (name "Net-(P1-Pad4)") (class "Default")
      (node (ref "P1") (pin "4") (pinfunction "4_4") (pintype "passive"))
      (node (ref "R13") (pin "2") (pinfunction "2_2") (pintype "passive"))
    )
    (net (code "20") (name "Net-(R10-Pad1)") (class "Default")
      (node (ref "R10") (pin "1") (pinfunction "1_1") (pintype "passive"))
      (node (ref "U2") (pin "1") (pinfunction "RG_1") (pintype "input"))
    )
    (net (code "21") (name "Net-(R10-Pad2)") (class "Default")
      (node (ref "R10") (pin "2") (pinfunction "2_2") (pintype "passive"))
      (node (ref "U2") (pin "8") (pinfunction "RG_8") (pintype "input"))
    )
    (net (code "22") (name "Net-(U1-ADDR)") (class "Default")
      (node (ref "R11") (pin "2") (pinfunction "2_2") (pintype "passive"))
      (node (ref "R20") (pin "1") (pinfunction "1_1") (pintype "passive"))
      (node (ref "U1") (pin "1") (pinfunction "ADDR_1") (pintype "input"))
    )
    (net (code "23") (name "Net-(U1-AIN0)") (class "Default")
      (node (ref "R18") (pin "2") (pinfunction "2_2") (pintype "passive"))
      (node (ref "U1") (pin "4") (pinfunction "AIN0_4") (pintype "input"))
    )
    (net (code "24") (name "Net-(U1-AIN1)") (class "Default")
      (node (ref "C6") (pin "1") (pinfunction "1_1") (pintype "passive"))
      (node (ref "R14") (pin "1") (pinfunction "1_1") (pintype "passive"))
      (node (ref "U1") (pin "5") (pinfunction "AIN1_5") (pintype "input"))
    )
    (net (code "25") (name "Net-(U1-SCL)") (class "Default")
      (node (ref "R17") (pin "1") (pinfunction "1_1") (pintype "passive"))
      (node (ref "U1") (pin "10") (pinfunction "SCL_10") (pintype "input"))
    )
    (net (code "26") (name "Net-(U1-SDA)") (class "Default")
      (node (ref "R15") (pin "1") (pinfunction "1_1") (pintype "passive"))
      (node (ref "U1") (pin "9") (pinfunction "SDA_9") (pintype "bidirectional"))
    )
    (net (code "27") (name "Net-(U1-VDD)") (class "Default")
      (node (ref "C3") (pin "2") (pinfunction "2_2") (pintype "passive"))
      (node (ref "R11") (pin "1") (pinfunction "1_1") (pintype "passive"))
      (node (ref "R6") (pin "1") (pinfunction "1_1") (pintype "passive"))
      (node (ref "R8") (pin "1") (pinfunction "1_1") (pintype "passive"))
      (node (ref "U1") (pin "8") (pinfunction "VDD_8") (pintype "power_in"))
    )
    (net (code "28") (name "Net-(U2-V+)") (class "Default")
      (node (ref "C2") (pin "2") (pinfunction "2_2") (pintype "passive"))
      (node (ref "R2") (pin "2") (pinfunction "2_2") (pintype "passive"))
      (node (ref "R4") (pin "2") (pinfunction "2_2") (pintype "passive"))
      (node (ref "R5") (pin "2") (pinfunction "2_2") (pintype "passive"))
      (node (ref "U2") (pin "7") (pinfunction "V+_7") (pintype "power_in"))
    )
    (net (code "29") (name "Net-(U2-VIN+)") (class "Default")
      (node (ref "C16") (pin "2") (pinfunction "2_2") (pintype "passive"))
      (node (ref "R16") (pin "1") (pinfunction "1_1") (pintype "passive"))
      (node (ref "U2") (pin "3") (pinfunction "VIN+_3") (pintype "input"))
    )
    (net (code "30") (name "Net-(U2-VIN-)") (class "Default")
      (node (ref "C16") (pin "1") (pinfunction "1_1") (pintype "passive"))
      (node (ref "R13") (pin "1") (pinfunction "1_1") (pintype "passive"))
      (node (ref "U2") (pin "2") (pinfunction "VIN-_2") (pintype "input"))
    )
    (net (code "31") (name "Net-(U2-VO)") (class "Default")
      (node (ref "R14") (pin "2") (pinfunction "2_2") (pintype "passive"))
      (node (ref "U2") (pin "6") (pinfunction "VO_6") (pintype "output"))
    )
    (net (code "32") (name "Net-(U3-ADDR)") (class "Default")
      (node (ref "R26") (pin "2") (pinfunction "2_2") (pintype "passive"))
      (node (ref "R33") (pin "1") (pinfunction "1_1") (pintype "passive"))
      (node (ref "U3") (pin "1") (pinfunction "ADDR_1") (pintype "input"))
    )
    (net (code "33") (name "Net-(U3-AIN0)") (class "Default")
      (node (ref "R32") (pin "2") (pinfunction "2_2") (pintype "passive"))
      (node (ref "U3") (pin "4") (pinfunction "AIN0_4") (pintype "input"))
    )
    (net (code "34") (name "Net-(U3-AIN1)") (class "Default")
      (node (ref "C11") (pin "1") (pinfunction "1_1") (pintype "passive"))
      (node (ref "R28") (pin "1") (pinfunction "1_1") (pintype "passive"))
      (node (ref "U3") (pin "5") (pinfunction "AIN1_5") (pintype "input"))
    )
    (net (code "35") (name "Net-(U3-SCL)") (class "Default")
      (node (ref "R31") (pin "1") (pinfunction "1_1") (pintype "passive"))
      (node (ref "U3") (pin "10") (pinfunction "SCL_10") (pintype "input"))
    )
    (net (code "36") (name "Net-(U3-SDA)") (class "Default")
      (node (ref "R29") (pin "1") (pinfunction "1_1") (pintype "passive"))
      (node (ref "U3") (pin "9") (pinfunction "SDA_9") (pintype "bidirectional"))
    )
    (net (code "37") (name "Net-(U3-VDD)") (class "Default")
      (node (ref "C10") (pin "2") (pinfunction "2_2") (pintype "passive"))
      (node (ref "R21") (pin "1") (pinfunction "1_1") (pintype "passive"))
      (node (ref "R22") (pin "1") (pinfunction "1_1") (pintype "passive"))
      (node (ref "R26") (pin "1") (pinfunction "1_1") (pintype "passive"))
      (node (ref "U3") (pin "8") (pinfunction "VDD_8") (pintype "power_in"))
    )
    (net (code "38") (name "Net-(U4A-VINA+)") (class "Default")
      (node (ref "R30") (pin "1") (pinfunction "1_1") (pintype "passive"))
      (node (ref "U4") (pin "3") (pinfunction "VINA+_3") (pintype "input"))
    )
    (net (code "39") (name "Net-(U4A-VINA-)") (class "Default")
      (node (ref "C8") (pin "2") (pinfunction "2_2") (pintype "passive"))
      (node (ref "R24") (pin "2") (pinfunction "2_2") (pintype "passive"))
      (node (ref "R27") (pin "2") (pinfunction "2_2") (pintype "passive"))
      (node (ref "U4") (pin "2") (pinfunction "VINA-_2") (pintype "input"))
    )
    (net (code "40") (name "Net-(U4A-VOUTA)") (class "Default")
      (node (ref "C8") (pin "1") (pinfunction "1_1") (pintype "passive"))
      (node (ref "R24") (pin "1") (pinfunction "1_1") (pintype "passive"))
      (node (ref "R28") (pin "2") (pinfunction "2_2") (pintype "passive"))
      (node (ref "U4") (pin "1") (pinfunction "VOUTA_1") (pintype "output"))
    )
    (net (code "41") (name "Net-(U4B-VINB+)") (class "Default")
      (node (ref "R46") (pin "1") (pinfunction "1_1") (pintype "passive"))
      (node (ref "U4") (pin "5") (pinfunction "VINB+_5") (pintype "input"))
    )
    (net (code "42") (name "Net-(U4B-VINB-)") (class "Default")
      (node (ref "C12") (pin "2") (pinfunction "2_2") (pintype "passive"))
      (node (ref "R37") (pin "2") (pinfunction "2_2") (pintype "passive"))
      (node (ref "R41") (pin "2") (pinfunction "2_2") (pintype "passive"))
      (node (ref "U4") (pin "6") (pinfunction "VINB-_6") (pintype "input"))
    )
    (net (code "43") (name "Net-(U4B-VOUTB)") (class "Default")
      (node (ref "C12") (pin "1") (pinfunction "1_1") (pintype "passive"))
      (node (ref "R37") (pin "1") (pinfunction "1_1") (pintype "passive"))
      (node (ref "R44") (pin "2") (pinfunction "2_2") (pintype "passive"))
      (node (ref "U4") (pin "7") (pinfunction "VOUTB_7") (pintype "output"))
    )
    (net (code "44") (name "Net-(U5-ADDR)") (class "Default")
      (node (ref "R40") (pin "2") (pinfunction "2_2") (pintype "passive"))
      (node (ref "R50") (pin "1") (pinfunction "1_1") (pintype "passive"))
      (node (ref "U5") (pin "1") (pinfunction "ADDR_1") (pintype "input"))
    )
    (net (code "45") (name "Net-(U5-AIN0)") (class "Default")
      (node (ref "R48") (pin "2") (pinfunction "2_2") (pintype "passive"))
      (node (ref "U5") (pin "4") (pinfunction "AIN0_4") (pintype "input"))
    )
    (net (code "46") (name "Net-(U5-AIN1)") (class "Default")
      (node (ref "C15") (pin "1") (pinfunction "1_1") (pintype "passive"))
      (node (ref "R44") (pin "1") (pinfunction "1_1") (pintype "passive"))
      (node (ref "U5") (pin "5") (pinfunction "AIN1_5") (pintype "input"))
    )
    (net (code "47") (name "Net-(U5-SCL)") (class "Default")
      (node (ref "R47") (pin "1") (pinfunction "1_1") (pintype "passive"))
      (node (ref "U5") (pin "10") (pinfunction "SCL_10") (pintype "input"))
    )
    (net (code "48") (name "Net-(U5-SDA)") (class "Default")
      (node (ref "R45") (pin "1") (pinfunction "1_1") (pintype "passive"))
      (node (ref "U5") (pin "9") (pinfunction "SDA_9") (pintype "bidirectional"))
    )
    (net (code "49") (name "Net-(U5-VDD)") (class "Default")
      (node (ref "C14") (pin "2") (pinfunction "2_2") (pintype "passive"))
      (node (ref "R36") (pin "1") (pinfunction "1_1") (pintype "passive"))
      (node (ref "R39") (pin "1") (pinfunction "1_1") (pintype "passive"))
      (node (ref "R40") (pin "1") (pinfunction "1_1") (pintype "passive"))
      (node (ref "U5") (pin "8") (pinfunction "VDD_8") (pintype "power_in"))
    )
    (net (code "50") (name "unconnected-(IC1-OUT_TAB-Pad4)") (class "Default")
      (node (ref "IC1") (pin "4") (pinfunction "OUT_TAB_4") (pintype "output+no_connect"))
    )
    (net (code "51") (name "unconnected-(U1-NC-Pad2)") (class "Default")
      (node (ref "U1") (pin "2") (pinfunction "NC_2") (pintype "passive+no_connect"))
    )
    (net (code "52") (name "unconnected-(U1-NC-Pad6)") (class "Default")
      (node (ref "U1") (pin "6") (pinfunction "NC_6") (pintype "passive+no_connect"))
    )
    (net (code "53") (name "unconnected-(U1-NC-Pad7)") (class "Default")
      (node (ref "U1") (pin "7") (pinfunction "NC_7") (pintype "passive+no_connect"))
    )
    (net (code "54") (name "unconnected-(U3-NC-Pad2)") (class "Default")
      (node (ref "U3") (pin "2") (pinfunction "NC_2") (pintype "passive+no_connect"))
    )
    (net (code "55") (name "unconnected-(U3-NC-Pad6)") (class "Default")
      (node (ref "U3") (pin "6") (pinfunction "NC_6") (pintype "passive+no_connect"))
    )
    (net (code "56") (name "unconnected-(U3-NC-Pad7)") (class "Default")
      (node (ref "U3") (pin "7") (pinfunction "NC_7") (pintype "passive+no_connect"))
    )
    (net (code "57") (name "unconnected-(U5-NC-Pad2)") (class "Default")
      (node (ref "U5") (pin "2") (pinfunction "NC_2") (pintype "passive+no_connect"))
    )
    (net (code "58") (name "unconnected-(U5-NC-Pad6)") (class "Default")
      (node (ref "U5") (pin "6") (pinfunction "NC_6") (pintype "passive+no_connect"))
    )
    (net (code "59") (name "unconnected-(U5-NC-Pad7)") (class "Default")
      (node (ref "U5") (pin "7") (pinfunction "NC_7") (pintype "passive+no_connect"))
    )
  )
)
